# verstaerker.net
KiCad netlist of a schematic drawn in EAGLE
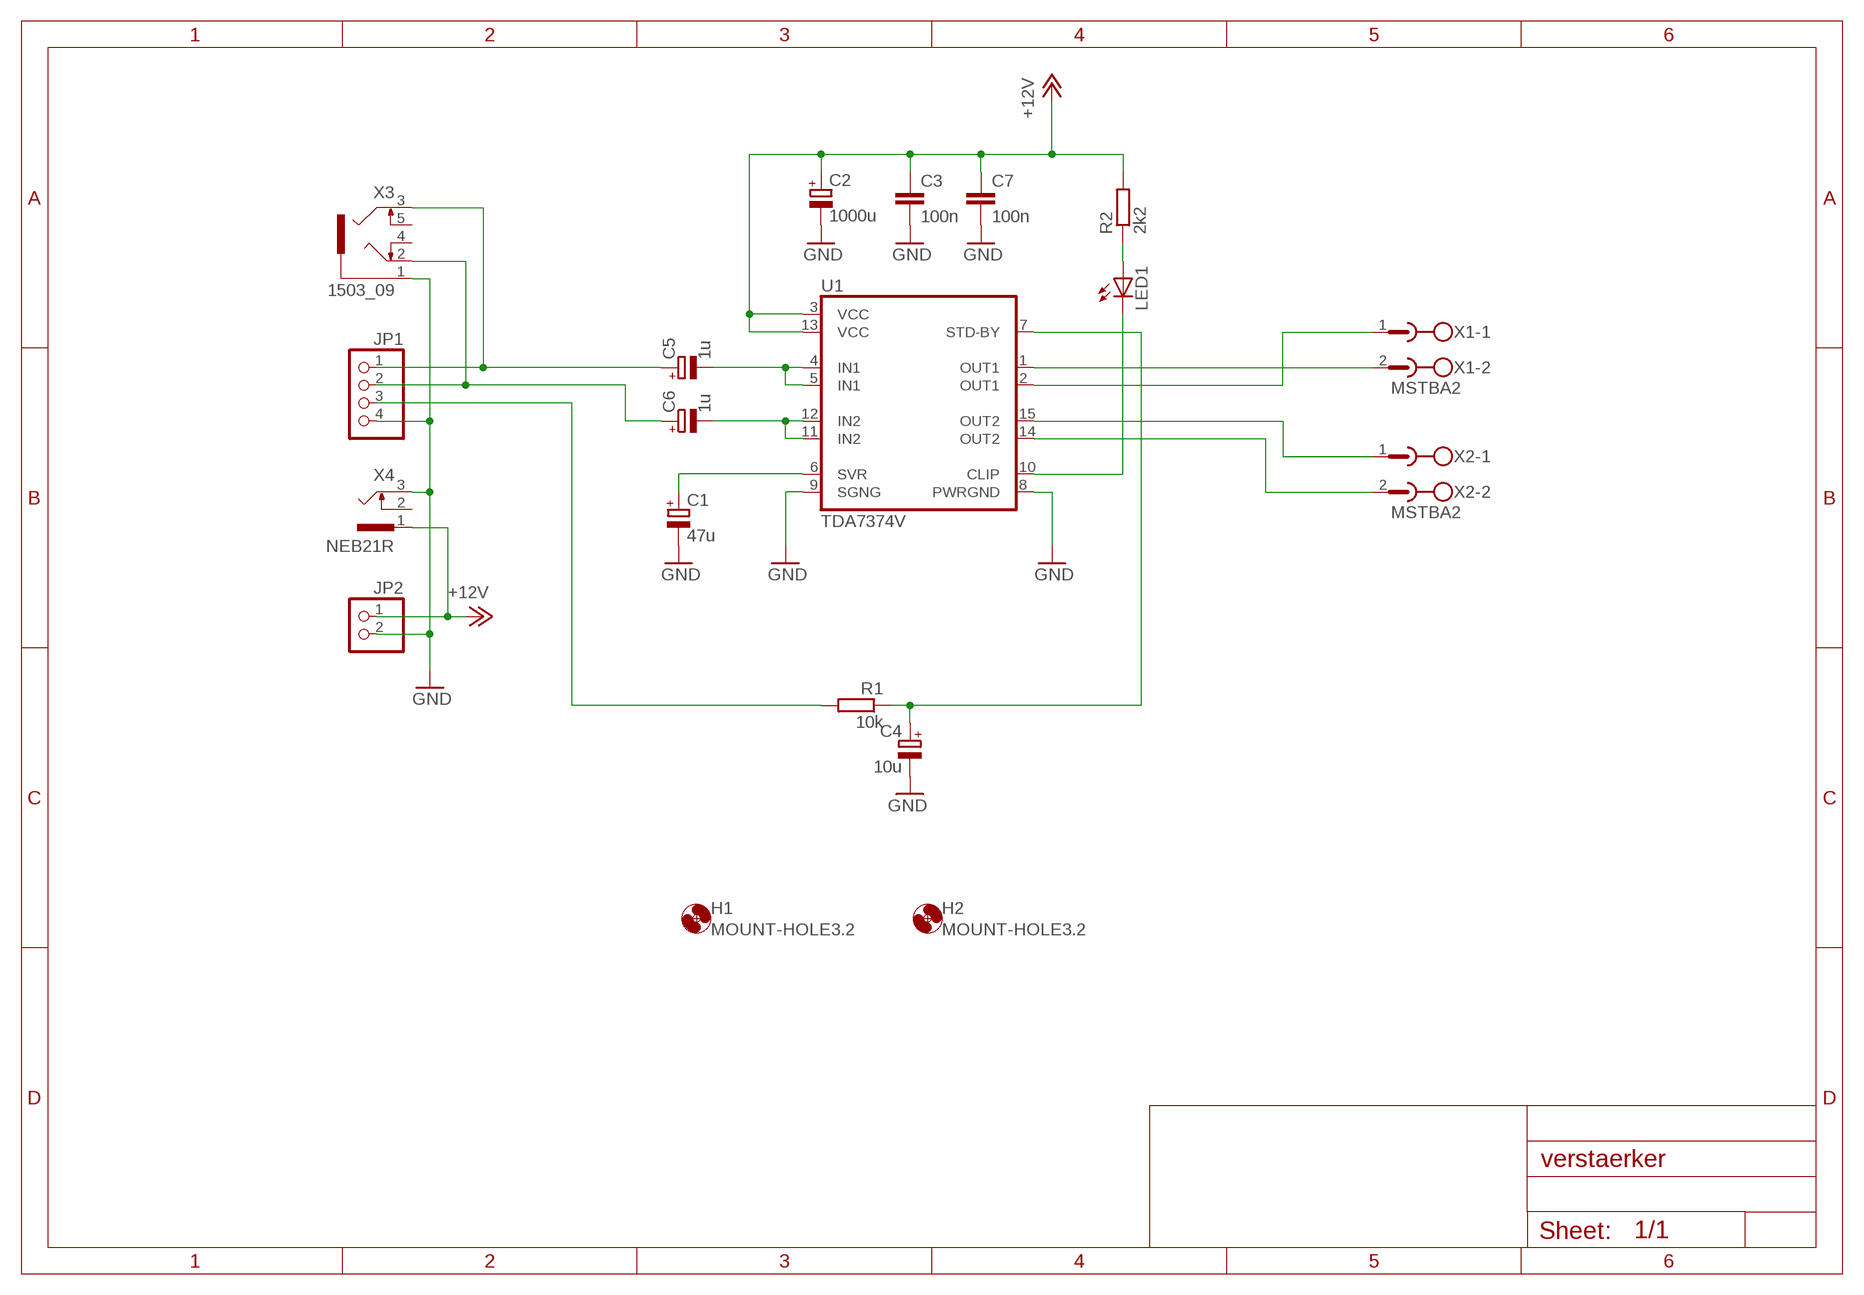
[diagram p0: schematic, sheet 1]

(export (version "E")
  (design (tool "Eeschema 10.0.6"))
  (components
    (comp (ref "C1")
      (value "47u")
      (footprint "eagle-import:E2,5-7")
      (libsource (lib "eagle-import") (part "CPOL-EUE2.5-7"))
    )
    (comp (ref "C2")
      (value "1000u")
      (footprint "eagle-import:E3,5-8")
      (libsource (lib "eagle-import") (part "CPOL-EUE3.5-8"))
    )
    (comp (ref "C3")
      (value "100n")
      (footprint "eagle-import:C050-025X075")
      (libsource (lib "eagle-import") (part "C-EU050-025X075"))
    )
    (comp (ref "C4")
      (value "10u")
      (footprint "eagle-import:E2-5")
      (libsource (lib "eagle-import") (part "CPOL-EUE2-5"))
    )
    (comp (ref "C5")
      (value "1u")
      (footprint "eagle-import:E2,5-5")
      (libsource (lib "eagle-import") (part "CPOL-EUE2.5-5"))
    )
    (comp (ref "C6")
      (value "1u")
      (footprint "eagle-import:E2,5-5")
      (libsource (lib "eagle-import") (part "CPOL-EUE2.5-5"))
    )
    (comp (ref "C7")
      (value "100n")
      (footprint "eagle-import:C050-025X075")
      (libsource (lib "eagle-import") (part "C-EU050-025X075"))
    )
    (comp (ref "H1")
      (value "MOUNT-HOLE3.2")
      (footprint "eagle-import:3,2")
      (libsource (lib "eagle-import") (part "MOUNT-HOLE3.2"))
    )
    (comp (ref "H2")
      (value "MOUNT-HOLE3.2")
      (footprint "eagle-import:3,2")
      (libsource (lib "eagle-import") (part "MOUNT-HOLE3.2"))
    )
    (comp (ref "JP1")
      (value "PINHD-1X4")
      (footprint "eagle-import:1X04")
      (libsource (lib "eagle-import") (part "PINHD-1X4"))
    )
    (comp (ref "JP2")
      (value "PINHD-1X2")
      (footprint "eagle-import:1X02")
      (libsource (lib "eagle-import") (part "PINHD-1X2"))
    )
    (comp (ref "LED1")
      (value "LED5MM")
      (footprint "eagle-import:LED5MM")
      (libsource (lib "eagle-import") (part "LED5MM"))
    )
    (comp (ref "R1")
      (value "10k")
      (footprint "eagle-import:R0805")
      (libsource (lib "eagle-import") (part "R-EU_R0805"))
    )
    (comp (ref "R2")
      (value "2k2")
      (footprint "eagle-import:R0805")
      (libsource (lib "eagle-import") (part "R-EU_R0805"))
    )
    (comp (ref "U1")
      (value "TDA7374V")
      (footprint "eagle-import:MULTIWATT-15V")
      (libsource (lib "eagle-import") (part "TDA7374V"))
    )
    (comp (ref "X1")
      (value "MSTBA2")
      (footprint "eagle-import:MSTBA2")
      (fields (field (name "MF") "FARNELL") (field (name "MPN") "1757242"))
      (libsource (lib "eagle-import") (part "MSTBA2"))
    )
    (comp (ref "X2")
      (value "MSTBA2")
      (footprint "eagle-import:MSTBA2")
      (fields (field (name "MF") "FARNELL") (field (name "MPN") "1757242"))
      (libsource (lib "eagle-import") (part "MSTBA2"))
    )
    (comp (ref "X3")
      (value "1503_09")
      (footprint "eagle-import:1503_09")
      (libsource (lib "eagle-import") (part "1503_09"))
    )
    (comp (ref "X4")
      (value "NEB21R")
      (footprint "eagle-import:NEB21R")
      (fields (field (name "MPN") "NEB 21 R"))
      (libsource (lib "eagle-import") (part "NEB21R"))
    )
  )
  (nets
    (net (code "1") (name "+12V") (class "Default")
      (node (ref "C2") (pin "+") (pinfunction "+_+") (pintype "passive"))
      (node (ref "C3") (pin "1") (pinfunction "1_1") (pintype "passive"))
      (node (ref "C7") (pin "1") (pinfunction "1_1") (pintype "passive"))
      (node (ref "JP2") (pin "1") (pinfunction "1_1") (pintype "passive"))
      (node (ref "R2") (pin "2") (pinfunction "2_2") (pintype "passive"))
      (node (ref "U1") (pin "13") (pinfunction "VCC_13") (pintype "power_in"))
      (node (ref "U1") (pin "3") (pinfunction "VCC_3") (pintype "power_in"))
      (node (ref "X4") (pin "1") (pinfunction "1_1") (pintype "passive"))
    )
    (net (code "2") (name "GND") (class "Default")
      (node (ref "C1") (pin "-") (pinfunction "-_-") (pintype "passive"))
      (node (ref "C2") (pin "-") (pinfunction "-_-") (pintype "passive"))
      (node (ref "C3") (pin "2") (pinfunction "2_2") (pintype "passive"))
      (node (ref "C4") (pin "-") (pinfunction "-_-") (pintype "passive"))
      (node (ref "C7") (pin "2") (pinfunction "2_2") (pintype "passive"))
      (node (ref "JP1") (pin "4") (pinfunction "4_4") (pintype "passive"))
      (node (ref "JP2") (pin "2") (pinfunction "2_2") (pintype "passive"))
      (node (ref "U1") (pin "8") (pinfunction "PWRGND_8") (pintype "power_in"))
      (node (ref "U1") (pin "9") (pinfunction "SGNG_9") (pintype "power_in"))
      (node (ref "X3") (pin "1") (pinfunction "1_1") (pintype "passive"))
      (node (ref "X4") (pin "3") (pinfunction "3_3") (pintype "passive"))
    )
    (net (code "3") (name "Net-(C5-Pad+)") (class "Default")
      (node (ref "C5") (pin "+") (pinfunction "+_+") (pintype "passive"))
      (node (ref "JP1") (pin "1") (pinfunction "1_1") (pintype "passive"))
      (node (ref "X3") (pin "3") (pinfunction "3_3") (pintype "passive"))
    )
    (net (code "4") (name "Net-(C5-Pad-)") (class "Default")
      (node (ref "C5") (pin "-") (pinfunction "-_-") (pintype "passive"))
      (node (ref "U1") (pin "4") (pinfunction "IN1_4") (pintype "input"))
      (node (ref "U1") (pin "5") (pinfunction "IN1_5") (pintype "input"))
    )
    (net (code "5") (name "Net-(C6-Pad+)") (class "Default")
      (node (ref "C6") (pin "+") (pinfunction "+_+") (pintype "passive"))
      (node (ref "JP1") (pin "2") (pinfunction "2_2") (pintype "passive"))
      (node (ref "X3") (pin "2") (pinfunction "2_2") (pintype "passive"))
    )
    (net (code "6") (name "Net-(C6-Pad-)") (class "Default")
      (node (ref "C6") (pin "-") (pinfunction "-_-") (pintype "passive"))
      (node (ref "U1") (pin "11") (pinfunction "IN2_11") (pintype "input"))
      (node (ref "U1") (pin "12") (pinfunction "IN2_12") (pintype "input"))
    )
    (net (code "7") (name "Net-(JP1-Pad3)") (class "Default")
      (node (ref "JP1") (pin "3") (pinfunction "3_3") (pintype "passive"))
      (node (ref "R1") (pin "2") (pinfunction "2_2") (pintype "passive"))
    )
    (net (code "8") (name "Net-(LED1-C)") (class "Default")
      (node (ref "LED1") (pin "K") (pinfunction "C_K") (pintype "passive"))
      (node (ref "U1") (pin "10") (pinfunction "CLIP_10") (pintype "passive"))
    )
    (net (code "9") (name "Net-(LED1-PadA)") (class "Default")
      (node (ref "LED1") (pin "A") (pinfunction "A_A") (pintype "passive"))
      (node (ref "R2") (pin "1") (pinfunction "1_1") (pintype "passive"))
    )
    (net (code "10") (name "Net-(U1-OUT1-Pad2)") (class "Default")
      (node (ref "U1") (pin "2") (pinfunction "OUT1_2") (pintype "output"))
      (node (ref "X1") (pin "1") (pinfunction "1_1") (pintype "passive"))
    )
    (net (code "11") (name "Net-(U1-OUT2-Pad15)") (class "Default")
      (node (ref "U1") (pin "15") (pinfunction "OUT2_15") (pintype "output"))
      (node (ref "X2") (pin "1") (pinfunction "1_1") (pintype "passive"))
    )
    (net (code "12") (name "Net-(U1-STD-BY)") (class "Default")
      (node (ref "C4") (pin "+") (pinfunction "+_+") (pintype "passive"))
      (node (ref "R1") (pin "1") (pinfunction "1_1") (pintype "passive"))
      (node (ref "U1") (pin "7") (pinfunction "STD-BY_7") (pintype "input"))
    )
    (net (code "13") (name "Net-(U1-SVR)") (class "Default")
      (node (ref "C1") (pin "+") (pinfunction "+_+") (pintype "passive"))
      (node (ref "U1") (pin "6") (pinfunction "SVR_6") (pintype "input"))
    )
    (net (code "14") (name "Net-(X1B-1)") (class "Default")
      (node (ref "U1") (pin "1") (pinfunction "OUT1_1") (pintype "output"))
      (node (ref "X1") (pin "2") (pinfunction "1_2") (pintype "passive"))
    )
    (net (code "15") (name "Net-(X2B-1)") (class "Default")
      (node (ref "U1") (pin "14") (pinfunction "OUT2_14") (pintype "output"))
      (node (ref "X2") (pin "2") (pinfunction "1_2") (pintype "passive"))
    )
    (net (code "16") (name "unconnected-(X3-Pad4)") (class "Default")
      (node (ref "X3") (pin "4") (pinfunction "4_4") (pintype "passive"))
    )
    (net (code "17") (name "unconnected-(X3-Pad5)") (class "Default")
      (node (ref "X3") (pin "5") (pinfunction "5_5") (pintype "passive"))
    )
    (net (code "18") (name "unconnected-(X4-Pad2)") (class "Default")
      (node (ref "X4") (pin "2") (pinfunction "2_2") (pintype "passive"))
    )
  )
)
